# cdf-modular-bridge-rev2.net
KiCad netlist of a schematic drawn in EAGLE
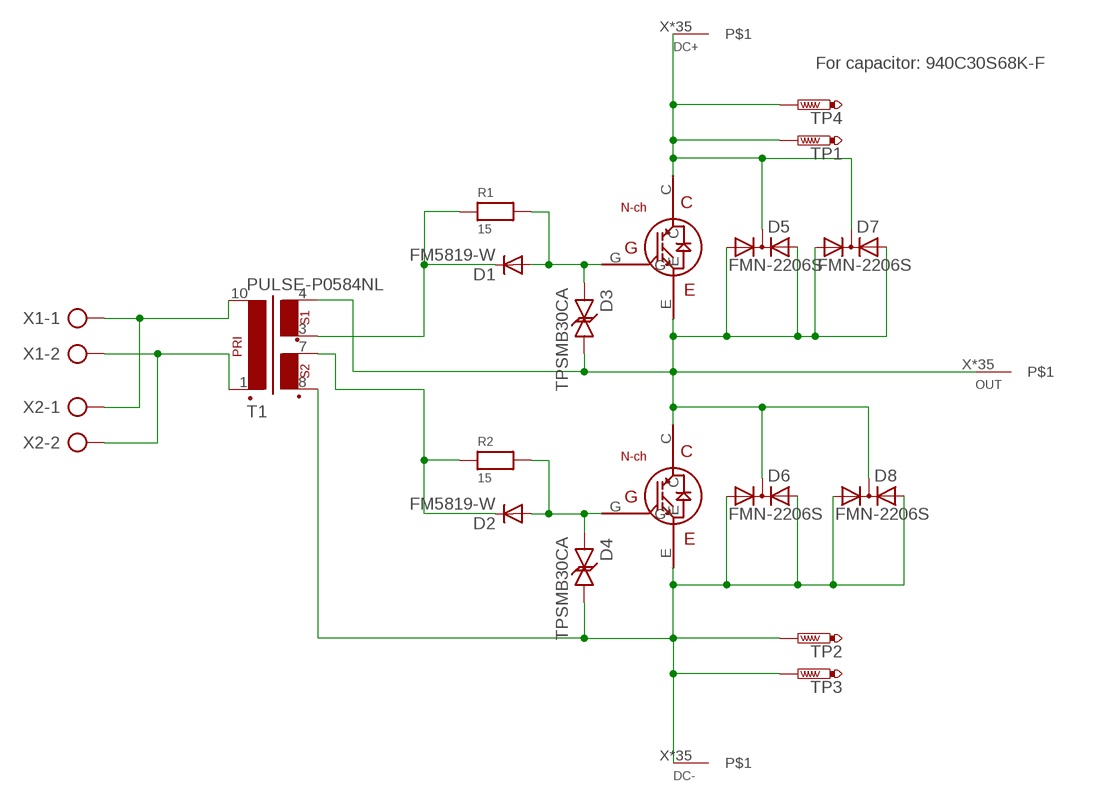
[diagram p0: schematic, sheet 1]

(export (version "E")
  (design (tool "Eeschema 10.0.6"))
  (components
    (comp (ref "D1")
      (value "FM5819-W")
      (footprint "eagle-import:DO214AC")
      (fields (field (name "MF") "Fairchild") (field (name "MPN") "S1A"))
      (libsource (lib "eagle-import") (part "S1A"))
    )
    (comp (ref "D2")
      (value "FM5819-W")
      (footprint "eagle-import:DO214AC")
      (fields (field (name "MF") "Fairchild") (field (name "MPN") "S1A"))
      (libsource (lib "eagle-import") (part "S1A"))
    )
    (comp (ref "D3")
      (value "TPSMB30CA")
      (footprint "eagle-import:TPSMB15CA")
      (libsource (lib "eagle-import") (part "TPSMB15CA"))
    )
    (comp (ref "D4")
      (value "TPSMB30CA")
      (footprint "eagle-import:TPSMB15CA")
      (libsource (lib "eagle-import") (part "TPSMB15CA"))
    )
    (comp (ref "D5")
      (value "FMN-2206S")
      (footprint "eagle-import:TO220ABS")
      (libsource (lib "eagle-import") (part "FMN-2206S"))
    )
    (comp (ref "D6")
      (value "FMN-2206S")
      (footprint "eagle-import:TO220ABS")
      (libsource (lib "eagle-import") (part "FMN-2206S"))
    )
    (comp (ref "D7")
      (value "FMN-2206S")
      (footprint "eagle-import:TO220ABS")
      (libsource (lib "eagle-import") (part "FMN-2206S"))
    )
    (comp (ref "D8")
      (value "FMN-2206S")
      (footprint "eagle-import:TO220ABS")
      (libsource (lib "eagle-import") (part "FMN-2206S"))
    )
    (comp (ref "DC+")
      (value "BIG-ASS-HOLE")
      (footprint "eagle-import:BIG-ASS-HOLE")
      (libsource (lib "eagle-import") (part "BIG-ASS-HOLE"))
    )
    (comp (ref "DC-")
      (value "BIG-ASS-HOLE")
      (footprint "eagle-import:BIG-ASS-HOLE")
      (libsource (lib "eagle-import") (part "BIG-ASS-HOLE"))
    )
    (comp (ref "OUT")
      (value "BIG-ASS-HOLE")
      (footprint "eagle-import:BIG-ASS-HOLE")
      (libsource (lib "eagle-import") (part "BIG-ASS-HOLE"))
    )
    (comp (ref "Q1")
      (value "Ixgh48n60a3")
      (footprint "eagle-import:IXGH40N60A")
      (libsource (lib "eagle-import") (part "IXGH40N60A"))
    )
    (comp (ref "Q2")
      (value "Ixgh48n60a3")
      (footprint "eagle-import:IXGH40N60A")
      (libsource (lib "eagle-import") (part "IXGH40N60A"))
    )
    (comp (ref "R1")
      (value "15")
      (footprint "eagle-import:1206")
      (libsource (lib "eagle-import") (part "RESISTOR1206"))
    )
    (comp (ref "R2")
      (value "15")
      (footprint "eagle-import:1206")
      (libsource (lib "eagle-import") (part "RESISTOR1206"))
    )
    (comp (ref "T1")
      (value "PULSE-P0584NL")
      (footprint "eagle-import:PULSE-P0584NL")
      (libsource (lib "eagle-import") (part "PULSE-P0584NL"))
    )
    (comp (ref "TP1")
      (value "PTR1PAD1-17")
      (footprint "eagle-import:P1-17")
      (libsource (lib "eagle-import") (part "PTR1PAD1-17"))
    )
    (comp (ref "TP2")
      (value "PTR1PAD1-17")
      (footprint "eagle-import:P1-17")
      (libsource (lib "eagle-import") (part "PTR1PAD1-17"))
    )
    (comp (ref "TP3")
      (value "PTR1PAD1-17")
      (footprint "eagle-import:P1-17")
      (libsource (lib "eagle-import") (part "PTR1PAD1-17"))
    )
    (comp (ref "TP4")
      (value "PTR1PAD1-17")
      (footprint "eagle-import:P1-17")
      (libsource (lib "eagle-import") (part "PTR1PAD1-17"))
    )
    (comp (ref "X1")
      (value "AK500/2")
      (footprint "eagle-import:AK500_2")
      (libsource (lib "eagle-import") (part "AK500/2"))
    )
    (comp (ref "X2")
      (value "AK500/2")
      (footprint "eagle-import:AK500_2")
      (libsource (lib "eagle-import") (part "AK500/2"))
    )
  )
  (nets
    (net (code "1") (name "Net-(D1-PadA)") (class "Default")
      (node (ref "D1") (pin "A") (pinfunction "A_A") (pintype "passive"))
      (node (ref "D3") (pin "P$1") (pinfunction "P$1_P$1") (pintype "passive"))
      (node (ref "Q1") (pin "G") (pinfunction "G_G") (pintype "bidirectional"))
      (node (ref "R1") (pin "2") (pinfunction "2_2") (pintype "passive"))
    )
    (net (code "2") (name "Net-(D2-PadA)") (class "Default")
      (node (ref "D2") (pin "A") (pinfunction "A_A") (pintype "passive"))
      (node (ref "D4") (pin "P$1") (pinfunction "P$1_P$1") (pintype "passive"))
      (node (ref "Q2") (pin "G") (pinfunction "G_G") (pintype "bidirectional"))
      (node (ref "R2") (pin "2") (pinfunction "2_2") (pintype "passive"))
    )
    (net (code "3") (name "Net-(D5-PadC)") (class "Default")
      (node (ref "D5") (pin "C") (pinfunction "C_C") (pintype "passive"))
      (node (ref "D7") (pin "C") (pinfunction "C_C") (pintype "passive"))
      (node (ref "DC+") (pin "X") (pinfunction "P$1_X") (pintype "bidirectional"))
      (node (ref "DC+") (pin "X@1") (pinfunction "P$1_X@1") (pintype "bidirectional"))
      (node (ref "DC+") (pin "X@10") (pinfunction "P$1_X@10") (pintype "bidirectional"))
      (node (ref "DC+") (pin "X@11") (pinfunction "P$1_X@11") (pintype "bidirectional"))
      (node (ref "DC+") (pin "X@12") (pinfunction "P$1_X@12") (pintype "bidirectional"))
      (node (ref "DC+") (pin "X@120") (pinfunction "P$1_X@120") (pintype "bidirectional"))
      (node (ref "DC+") (pin "X@13") (pinfunction "P$1_X@13") (pintype "bidirectional"))
      (node (ref "DC+") (pin "X@14") (pinfunction "P$1_X@14") (pintype "bidirectional"))
      (node (ref "DC+") (pin "X@15") (pinfunction "P$1_X@15") (pintype "bidirectional"))
      (node (ref "DC+") (pin "X@16") (pinfunction "P$1_X@16") (pintype "bidirectional"))
      (node (ref "DC+") (pin "X@17") (pinfunction "P$1_X@17") (pintype "bidirectional"))
      (node (ref "DC+") (pin "X@18") (pinfunction "P$1_X@18") (pintype "bidirectional"))
      (node (ref "DC+") (pin "X@19") (pinfunction "P$1_X@19") (pintype "bidirectional"))
      (node (ref "DC+") (pin "X@2") (pinfunction "P$1_X@2") (pintype "bidirectional"))
      (node (ref "DC+") (pin "X@20") (pinfunction "P$1_X@20") (pintype "bidirectional"))
      (node (ref "DC+") (pin "X@21") (pinfunction "P$1_X@21") (pintype "bidirectional"))
      (node (ref "DC+") (pin "X@22") (pinfunction "P$1_X@22") (pintype "bidirectional"))
      (node (ref "DC+") (pin "X@23") (pinfunction "P$1_X@23") (pintype "bidirectional"))
      (node (ref "DC+") (pin "X@24") (pinfunction "P$1_X@24") (pintype "bidirectional"))
      (node (ref "DC+") (pin "X@25") (pinfunction "P$1_X@25") (pintype "bidirectional"))
      (node (ref "DC+") (pin "X@26") (pinfunction "P$1_X@26") (pintype "bidirectional"))
      (node (ref "DC+") (pin "X@27") (pinfunction "P$1_X@27") (pintype "bidirectional"))
      (node (ref "DC+") (pin "X@28") (pinfunction "P$1_X@28") (pintype "bidirectional"))
      (node (ref "DC+") (pin "X@29") (pinfunction "P$1_X@29") (pintype "bidirectional"))
      (node (ref "DC+") (pin "X@3") (pinfunction "P$1_X@3") (pintype "bidirectional"))
      (node (ref "DC+") (pin "X@30") (pinfunction "P$1_X@30") (pintype "bidirectional"))
      (node (ref "DC+") (pin "X@31") (pinfunction "P$1_X@31") (pintype "bidirectional"))
      (node (ref "DC+") (pin "X@32") (pinfunction "P$1_X@32") (pintype "bidirectional"))
      (node (ref "DC+") (pin "X@34") (pinfunction "P$1_X@34") (pintype "bidirectional"))
      (node (ref "DC+") (pin "X@4") (pinfunction "P$1_X@4") (pintype "bidirectional"))
      (node (ref "DC+") (pin "X@5") (pinfunction "P$1_X@5") (pintype "bidirectional"))
      (node (ref "DC+") (pin "X@6") (pinfunction "P$1_X@6") (pintype "bidirectional"))
      (node (ref "DC+") (pin "X@7") (pinfunction "P$1_X@7") (pintype "bidirectional"))
      (node (ref "DC+") (pin "X@8") (pinfunction "P$1_X@8") (pintype "bidirectional"))
      (node (ref "DC+") (pin "X@9") (pinfunction "P$1_X@9") (pintype "bidirectional"))
      (node (ref "Q1") (pin "C") (pinfunction "C_C") (pintype "bidirectional"))
      (node (ref "TP1") (pin "TP") (pinfunction "TP_TP") (pintype "input"))
      (node (ref "TP4") (pin "TP") (pinfunction "TP_TP") (pintype "input"))
    )
    (net (code "4") (name "Net-(T1-PRI_NEG)") (class "Default")
      (node (ref "T1") (pin "10") (pinfunction "PRI_NEG_10") (pintype "passive"))
      (node (ref "X1") (pin "1") (pinfunction "KL_1") (pintype "passive"))
      (node (ref "X2") (pin "1") (pinfunction "KL_1") (pintype "passive"))
    )
    (net (code "5") (name "Net-(T1-PRI_POS)") (class "Default")
      (node (ref "T1") (pin "1") (pinfunction "PRI_POS_1") (pintype "passive"))
      (node (ref "X1") (pin "2") (pinfunction "KL_2") (pintype "passive"))
      (node (ref "X2") (pin "2") (pinfunction "KL_2") (pintype "passive"))
    )
    (net (code "6") (name "Net-(T1-SEC1_NEG)") (class "Default")
      (node (ref "D3") (pin "P$2") (pinfunction "P$2_P$2") (pintype "passive"))
      (node (ref "D5") (pin "A1") (pinfunction "A1_A1") (pintype "passive"))
      (node (ref "D5") (pin "A2") (pinfunction "A2_A2") (pintype "passive"))
      (node (ref "D6") (pin "C") (pinfunction "C_C") (pintype "passive"))
      (node (ref "D7") (pin "A1") (pinfunction "A1_A1") (pintype "passive"))
      (node (ref "D7") (pin "A2") (pinfunction "A2_A2") (pintype "passive"))
      (node (ref "D8") (pin "C") (pinfunction "C_C") (pintype "passive"))
      (node (ref "OUT") (pin "X") (pinfunction "P$1_X") (pintype "bidirectional"))
      (node (ref "OUT") (pin "X@1") (pinfunction "P$1_X@1") (pintype "bidirectional"))
      (node (ref "OUT") (pin "X@10") (pinfunction "P$1_X@10") (pintype "bidirectional"))
      (node (ref "OUT") (pin "X@11") (pinfunction "P$1_X@11") (pintype "bidirectional"))
      (node (ref "OUT") (pin "X@12") (pinfunction "P$1_X@12") (pintype "bidirectional"))
      (node (ref "OUT") (pin "X@120") (pinfunction "P$1_X@120") (pintype "bidirectional"))
      (node (ref "OUT") (pin "X@13") (pinfunction "P$1_X@13") (pintype "bidirectional"))
      (node (ref "OUT") (pin "X@14") (pinfunction "P$1_X@14") (pintype "bidirectional"))
      (node (ref "OUT") (pin "X@15") (pinfunction "P$1_X@15") (pintype "bidirectional"))
      (node (ref "OUT") (pin "X@16") (pinfunction "P$1_X@16") (pintype "bidirectional"))
      (node (ref "OUT") (pin "X@17") (pinfunction "P$1_X@17") (pintype "bidirectional"))
      (node (ref "OUT") (pin "X@18") (pinfunction "P$1_X@18") (pintype "bidirectional"))
      (node (ref "OUT") (pin "X@19") (pinfunction "P$1_X@19") (pintype "bidirectional"))
      (node (ref "OUT") (pin "X@2") (pinfunction "P$1_X@2") (pintype "bidirectional"))
      (node (ref "OUT") (pin "X@20") (pinfunction "P$1_X@20") (pintype "bidirectional"))
      (node (ref "OUT") (pin "X@21") (pinfunction "P$1_X@21") (pintype "bidirectional"))
      (node (ref "OUT") (pin "X@22") (pinfunction "P$1_X@22") (pintype "bidirectional"))
      (node (ref "OUT") (pin "X@23") (pinfunction "P$1_X@23") (pintype "bidirectional"))
      (node (ref "OUT") (pin "X@24") (pinfunction "P$1_X@24") (pintype "bidirectional"))
      (node (ref "OUT") (pin "X@25") (pinfunction "P$1_X@25") (pintype "bidirectional"))
      (node (ref "OUT") (pin "X@26") (pinfunction "P$1_X@26") (pintype "bidirectional"))
      (node (ref "OUT") (pin "X@27") (pinfunction "P$1_X@27") (pintype "bidirectional"))
      (node (ref "OUT") (pin "X@28") (pinfunction "P$1_X@28") (pintype "bidirectional"))
      (node (ref "OUT") (pin "X@29") (pinfunction "P$1_X@29") (pintype "bidirectional"))
      (node (ref "OUT") (pin "X@3") (pinfunction "P$1_X@3") (pintype "bidirectional"))
      (node (ref "OUT") (pin "X@30") (pinfunction "P$1_X@30") (pintype "bidirectional"))
      (node (ref "OUT") (pin "X@31") (pinfunction "P$1_X@31") (pintype "bidirectional"))
      (node (ref "OUT") (pin "X@32") (pinfunction "P$1_X@32") (pintype "bidirectional"))
      (node (ref "OUT") (pin "X@34") (pinfunction "P$1_X@34") (pintype "bidirectional"))
      (node (ref "OUT") (pin "X@4") (pinfunction "P$1_X@4") (pintype "bidirectional"))
      (node (ref "OUT") (pin "X@5") (pinfunction "P$1_X@5") (pintype "bidirectional"))
      (node (ref "OUT") (pin "X@6") (pinfunction "P$1_X@6") (pintype "bidirectional"))
      (node (ref "OUT") (pin "X@7") (pinfunction "P$1_X@7") (pintype "bidirectional"))
      (node (ref "OUT") (pin "X@8") (pinfunction "P$1_X@8") (pintype "bidirectional"))
      (node (ref "OUT") (pin "X@9") (pinfunction "P$1_X@9") (pintype "bidirectional"))
      (node (ref "Q1") (pin "E") (pinfunction "E_E") (pintype "bidirectional"))
      (node (ref "Q2") (pin "C") (pinfunction "C_C") (pintype "bidirectional"))
      (node (ref "T1") (pin "4") (pinfunction "SEC1_NEG_4") (pintype "passive"))
    )
    (net (code "7") (name "Net-(T1-SEC1_POS)") (class "Default")
      (node (ref "D1") (pin "C") (pinfunction "C_C") (pintype "passive"))
      (node (ref "R1") (pin "1") (pinfunction "1_1") (pintype "passive"))
      (node (ref "T1") (pin "3") (pinfunction "SEC1_POS_3") (pintype "passive"))
    )
    (net (code "8") (name "Net-(T1-SEC2_NEG)") (class "Default")
      (node (ref "D2") (pin "C") (pinfunction "C_C") (pintype "passive"))
      (node (ref "R2") (pin "1") (pinfunction "1_1") (pintype "passive"))
      (node (ref "T1") (pin "7") (pinfunction "SEC2_NEG_7") (pintype "passive"))
    )
    (net (code "9") (name "Net-(T1-SEC2_POS)") (class "Default")
      (node (ref "D4") (pin "P$2") (pinfunction "P$2_P$2") (pintype "passive"))
      (node (ref "D6") (pin "A1") (pinfunction "A1_A1") (pintype "passive"))
      (node (ref "D6") (pin "A2") (pinfunction "A2_A2") (pintype "passive"))
      (node (ref "D8") (pin "A1") (pinfunction "A1_A1") (pintype "passive"))
      (node (ref "D8") (pin "A2") (pinfunction "A2_A2") (pintype "passive"))
      (node (ref "DC-") (pin "X") (pinfunction "P$1_X") (pintype "bidirectional"))
      (node (ref "DC-") (pin "X@1") (pinfunction "P$1_X@1") (pintype "bidirectional"))
      (node (ref "DC-") (pin "X@10") (pinfunction "P$1_X@10") (pintype "bidirectional"))
      (node (ref "DC-") (pin "X@11") (pinfunction "P$1_X@11") (pintype "bidirectional"))
      (node (ref "DC-") (pin "X@12") (pinfunction "P$1_X@12") (pintype "bidirectional"))
      (node (ref "DC-") (pin "X@120") (pinfunction "P$1_X@120") (pintype "bidirectional"))
      (node (ref "DC-") (pin "X@13") (pinfunction "P$1_X@13") (pintype "bidirectional"))
      (node (ref "DC-") (pin "X@14") (pinfunction "P$1_X@14") (pintype "bidirectional"))
      (node (ref "DC-") (pin "X@15") (pinfunction "P$1_X@15") (pintype "bidirectional"))
      (node (ref "DC-") (pin "X@16") (pinfunction "P$1_X@16") (pintype "bidirectional"))
      (node (ref "DC-") (pin "X@17") (pinfunction "P$1_X@17") (pintype "bidirectional"))
      (node (ref "DC-") (pin "X@18") (pinfunction "P$1_X@18") (pintype "bidirectional"))
      (node (ref "DC-") (pin "X@19") (pinfunction "P$1_X@19") (pintype "bidirectional"))
      (node (ref "DC-") (pin "X@2") (pinfunction "P$1_X@2") (pintype "bidirectional"))
      (node (ref "DC-") (pin "X@20") (pinfunction "P$1_X@20") (pintype "bidirectional"))
      (node (ref "DC-") (pin "X@21") (pinfunction "P$1_X@21") (pintype "bidirectional"))
      (node (ref "DC-") (pin "X@22") (pinfunction "P$1_X@22") (pintype "bidirectional"))
      (node (ref "DC-") (pin "X@23") (pinfunction "P$1_X@23") (pintype "bidirectional"))
      (node (ref "DC-") (pin "X@24") (pinfunction "P$1_X@24") (pintype "bidirectional"))
      (node (ref "DC-") (pin "X@25") (pinfunction "P$1_X@25") (pintype "bidirectional"))
      (node (ref "DC-") (pin "X@26") (pinfunction "P$1_X@26") (pintype "bidirectional"))
      (node (ref "DC-") (pin "X@27") (pinfunction "P$1_X@27") (pintype "bidirectional"))
      (node (ref "DC-") (pin "X@28") (pinfunction "P$1_X@28") (pintype "bidirectional"))
      (node (ref "DC-") (pin "X@29") (pinfunction "P$1_X@29") (pintype "bidirectional"))
      (node (ref "DC-") (pin "X@3") (pinfunction "P$1_X@3") (pintype "bidirectional"))
      (node (ref "DC-") (pin "X@30") (pinfunction "P$1_X@30") (pintype "bidirectional"))
      (node (ref "DC-") (pin "X@31") (pinfunction "P$1_X@31") (pintype "bidirectional"))
      (node (ref "DC-") (pin "X@32") (pinfunction "P$1_X@32") (pintype "bidirectional"))
      (node (ref "DC-") (pin "X@34") (pinfunction "P$1_X@34") (pintype "bidirectional"))
      (node (ref "DC-") (pin "X@4") (pinfunction "P$1_X@4") (pintype "bidirectional"))
      (node (ref "DC-") (pin "X@5") (pinfunction "P$1_X@5") (pintype "bidirectional"))
      (node (ref "DC-") (pin "X@6") (pinfunction "P$1_X@6") (pintype "bidirectional"))
      (node (ref "DC-") (pin "X@7") (pinfunction "P$1_X@7") (pintype "bidirectional"))
      (node (ref "DC-") (pin "X@8") (pinfunction "P$1_X@8") (pintype "bidirectional"))
      (node (ref "DC-") (pin "X@9") (pinfunction "P$1_X@9") (pintype "bidirectional"))
      (node (ref "Q2") (pin "E") (pinfunction "E_E") (pintype "bidirectional"))
      (node (ref "T1") (pin "8") (pinfunction "SEC2_POS_8") (pintype "passive"))
      (node (ref "TP2") (pin "TP") (pinfunction "TP_TP") (pintype "input"))
      (node (ref "TP3") (pin "TP") (pinfunction "TP_TP") (pintype "input"))
    )
  )
)
